# Sheet1.net
KiCad netlist of a schematic drawn in Altium Designer
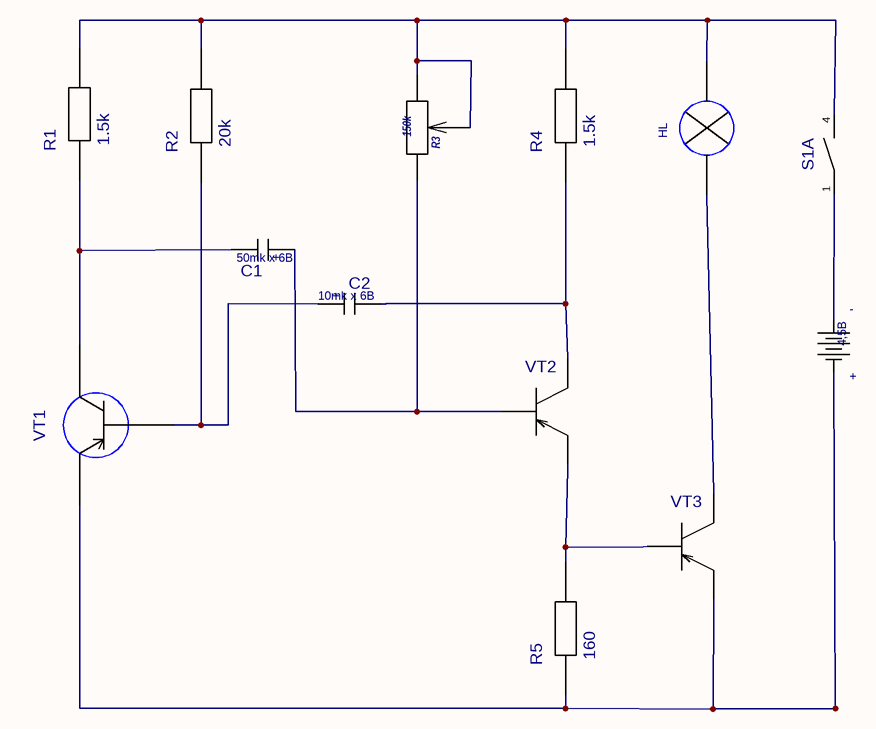
[diagram p0: Sheet1.SCHDOC]

(export (version "E")
  (design (tool "Eeschema 10.0.6"))
  (components
    (comp (ref "B1")
      (value "4,5B")
      (footprint "BATAR")
      (description "BATAR")
      (libsource (lib "*") (part "BATAR"))
    )
    (comp (ref "C1")
      (value "50mk x 6B")
      (footprint "CAP2")
      (description "CAP2")
      (libsource (lib "*") (part "CAP2"))
    )
    (comp (ref "C2")
      (value "10mk x 6B")
      (footprint "CAP2")
      (description "CAP2")
      (libsource (lib "*") (part "CAP2"))
    )
    (comp (ref "HL") (value "HL") (footprint "HL") (libsource (lib "*") (part "HL")))
    (comp (ref "R1")
      (value "1.5k")
      (footprint "SMD_08_05")
      (description "RES_08_05")
      (libsource (lib "*") (part "RES_08_05"))
    )
    (comp (ref "R2")
      (value "20k")
      (footprint "SMD_08_05")
      (description "RES_08_05")
      (libsource (lib "*") (part "RES_08_05"))
    )
    (comp (ref "R3")
      (value "150k")
      (footprint "СП3-38В")
      (description "СП3-38В")
      (libsource (lib "*") (part "СП3-38В"))
    )
    (comp (ref "R4")
      (value "1.5k")
      (footprint "SMD_08_05")
      (description "RES_08_05")
      (libsource (lib "*") (part "RES_08_05"))
    )
    (comp (ref "R5")
      (value "160")
      (footprint "SMD_08_05")
      (description "RES_08_05")
      (libsource (lib "*") (part "RES_08_05"))
    )
    (comp (ref "S1") (value "БДМ1-2") (footprint "BDM1-2") (libsource (lib "*") (part "БДМ1-2")))
    (comp (ref "VT1") (value "КТ361") (footprint "КТ315") (libsource (lib "*") (part "КТ361")))
    (comp (ref "VT2") (value "KT816") (footprint "KT27") (libsource (lib "*") (part "KT816")))
    (comp (ref "VT3") (value "KT816") (footprint "KT27") (libsource (lib "*") (part "KT816")))
  )
  (nets
    (net (code "1") (name "Net-(B1-MINUS)") (class "Default")
      (node (ref "B1") (pin "2") (pinfunction "MINUS_2") (pintype "passive"))
      (node (ref "R5") (pin "1") (pintype "passive"))
      (node (ref "VT1") (pin "3") (pinfunction "A3_3") (pintype "passive"))
      (node (ref "VT3") (pin "1") (pinfunction "E_1") (pintype "passive"))
    )
    (net (code "2") (name "Net-(B1-PLUS)") (class "Default")
      (node (ref "B1") (pin "1") (pinfunction "PLUS_1") (pintype "passive"))
      (node (ref "S1") (pin "1") (pinfunction "I/O1_1") (pintype "passive"))
    )
    (net (code "3") (name "Net-(S1A-I{slash}O2)") (class "Default")
      (node (ref "HL") (pin "2") (pinfunction "2_2") (pintype "passive"))
      (node (ref "R1") (pin "2") (pintype "passive"))
      (node (ref "R2") (pin "2") (pintype "passive"))
      (node (ref "R3") (pin "1") (pinfunction "1_1") (pintype "passive"))
      (node (ref "R3") (pin "3") (pinfunction "3_3") (pintype "passive"))
      (node (ref "R4") (pin "2") (pintype "passive"))
      (node (ref "S1") (pin "4") (pinfunction "I/O2_4") (pintype "passive"))
    )
    (net (code "4") (name "Net-(VT1-A1)") (class "Default")
      (node (ref "C2") (pin "1") (pinfunction "1_1") (pintype "passive"))
      (node (ref "R2") (pin "1") (pintype "passive"))
      (node (ref "VT1") (pin "1") (pinfunction "A1_1") (pintype "passive"))
    )
    (net (code "5") (name "Net-(VT1-A2)") (class "Default")
      (node (ref "C1") (pin "2") (pinfunction "2_2") (pintype "passive"))
      (node (ref "R1") (pin "1") (pintype "passive"))
      (node (ref "VT1") (pin "2") (pinfunction "A2_2") (pintype "passive"))
    )
    (net (code "6") (name "Net-(VT2-B)") (class "Default")
      (node (ref "C1") (pin "1") (pinfunction "1_1") (pintype "passive"))
      (node (ref "R3") (pin "2") (pinfunction "2_2") (pintype "passive"))
      (node (ref "VT2") (pin "2") (pinfunction "B_2") (pintype "passive"))
    )
    (net (code "7") (name "Net-(VT2-E)") (class "Default")
      (node (ref "R5") (pin "2") (pintype "passive"))
      (node (ref "VT2") (pin "1") (pinfunction "E_1") (pintype "passive"))
      (node (ref "VT3") (pin "2") (pinfunction "B_2") (pintype "passive"))
    )
    (net (code "8") (name "Net-(VT2-K)") (class "Default")
      (node (ref "C2") (pin "2") (pinfunction "2_2") (pintype "passive"))
      (node (ref "R4") (pin "1") (pintype "passive"))
      (node (ref "VT2") (pin "3") (pinfunction "K_3") (pintype "passive"))
    )
    (net (code "9") (name "Net-(VT3-K)") (class "Default")
      (node (ref "HL") (pin "1") (pinfunction "1_1") (pintype "passive"))
      (node (ref "VT3") (pin "3") (pinfunction "K_3") (pintype "passive"))
    )
  )
)
